# Micro-OLED-Breakout.net
KiCad netlist of a schematic drawn in EAGLE
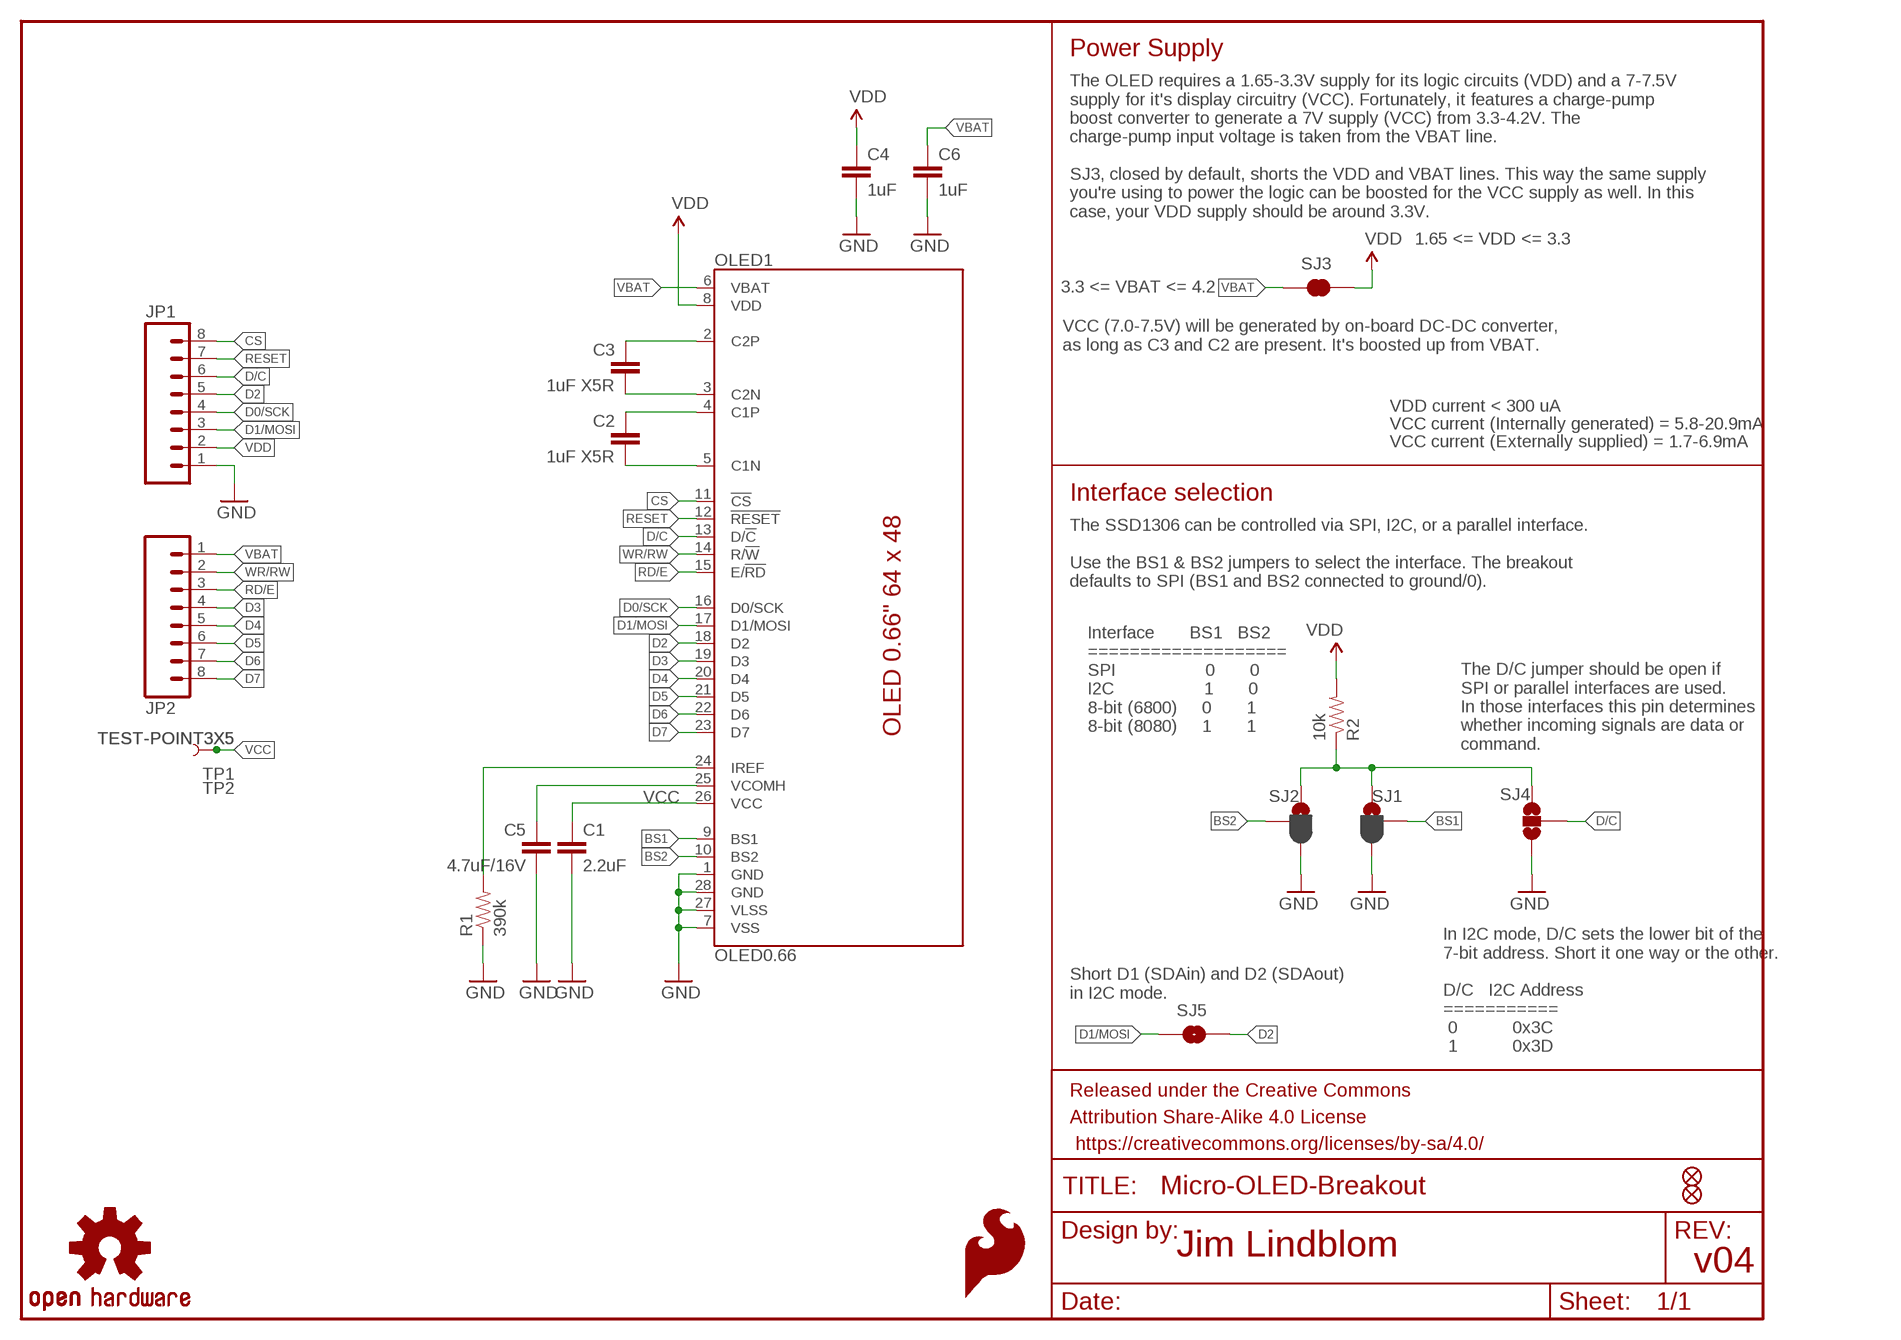
[diagram p0: schematic, sheet 1]

(export (version "E")
  (design (tool "Eeschema 10.0.6"))
  (components
    (comp (ref "C1")
      (value "2.2uF")
      (footprint "eagle-import:0805")
      (libsource (lib "eagle-import") (part "CAP0805"))
    )
    (comp (ref "C2")
      (value "1uF X5R")
      (footprint "eagle-import:0805")
      (libsource (lib "eagle-import") (part "CAP0805"))
    )
    (comp (ref "C3")
      (value "1uF X5R")
      (footprint "eagle-import:0805")
      (libsource (lib "eagle-import") (part "CAP0805"))
    )
    (comp (ref "C4")
      (value "1uF")
      (footprint "eagle-import:0603-CAP")
      (libsource (lib "eagle-import") (part "CAP0603-CAP"))
    )
    (comp (ref "C5")
      (value "4.7uF/16V")
      (footprint "eagle-import:1206")
      (libsource (lib "eagle-import") (part "CAP1206"))
    )
    (comp (ref "C6")
      (value "1uF")
      (footprint "eagle-import:0603-CAP")
      (libsource (lib "eagle-import") (part "CAP0603-CAP"))
    )
    (comp (ref "FID1")
      (value "FIDUCIAL1X2")
      (footprint "eagle-import:FIDUCIAL-1X2")
      (libsource (lib "eagle-import") (part "FIDUCIAL1X2"))
    )
    (comp (ref "FID2")
      (value "FIDUCIAL1X2")
      (footprint "eagle-import:FIDUCIAL-1X2")
      (libsource (lib "eagle-import") (part "FIDUCIAL1X2"))
    )
    (comp (ref "FRAME1")
      (value "FRAME-LETTER")
      (footprint "eagle-import:CREATIVE_COMMONS")
      (libsource (lib "eagle-import") (part "FRAME-LETTER"))
    )
    (comp (ref "JP1")
      (value "M08")
      (footprint "eagle-import:1X08_PIN1_NO_SILK")
      (libsource (lib "eagle-import") (part "M08"))
    )
    (comp (ref "JP2")
      (value "M08")
      (footprint "eagle-import:1X08_PIN1_NO_SILK")
      (libsource (lib "eagle-import") (part "M08"))
    )
    (comp (ref "LOGO3")
      (value "OSHW-LOGOS")
      (footprint "eagle-import:OSHW-LOGO-S")
      (libsource (lib "eagle-import") (part "OSHW-LOGOS"))
    )
    (comp (ref "LOGO4")
      (value "SFE_LOGO_FLAME.1_INCH")
      (footprint "eagle-import:SFE_LOGO_FLAME_.1")
      (libsource (lib "eagle-import") (part "SFE_LOGO_FLAME.1_INCH"))
    )
    (comp (ref "OLED1")
      (value "OLED0.66")
      (footprint "eagle-import:OLED-0.66-64X48")
      (libsource (lib "eagle-import") (part "OLED0.66"))
    )
    (comp (ref "R1")
      (value "390k")
      (footprint "eagle-import:0603-RES")
      (libsource (lib "eagle-import") (part "RESISTOR0603-RES"))
    )
    (comp (ref "R2")
      (value "10k")
      (footprint "eagle-import:0603-RES")
      (libsource (lib "eagle-import") (part "RESISTOR0603-RES"))
    )
    (comp (ref "SJ1")
      (value "BS1")
      (footprint "eagle-import:PAD-JUMPER-3-2OF3_NC_BY_PASTE_YES_SILK_FULL_BOX")
      (libsource (lib "eagle-import") (part "JUMPER-PAD-3-2OF3_NC_BY_PASTE"))
    )
    (comp (ref "SJ2")
      (value "BS2")
      (footprint "eagle-import:PAD-JUMPER-3-2OF3_NC_BY_PASTE_YES_SILK_FULL_BOX")
      (libsource (lib "eagle-import") (part "JUMPER-PAD-3-2OF3_NC_BY_PASTE"))
    )
    (comp (ref "SJ3")
      (value "JUMPER-PAD-2-NC_BY_TRACENO_SILK")
      (footprint "eagle-import:PAD-JUMPER-2-NC_BY_TRACE_NO_SILK")
      (libsource (lib "eagle-import") (part "JUMPER-PAD-2-NC_BY_TRACENO_SILK"))
    )
    (comp (ref "SJ4")
      (value "JUMPER-PAD-3-NOTIGHT")
      (footprint "eagle-import:PAD-JUMPER-3-NO-TIGHT")
      (libsource (lib "eagle-import") (part "JUMPER-PAD-3-NOTIGHT"))
    )
    (comp (ref "SJ5")
      (value "JUMPER-PAD-2-NOYES_SILK")
      (footprint "eagle-import:PAD-JUMPER-2-NO_YES_SILK")
      (libsource (lib "eagle-import") (part "JUMPER-PAD-2-NOYES_SILK"))
    )
    (comp (ref "TP1")
      (value "TEST-POINT3X5")
      (footprint "eagle-import:PAD.03X.05")
      (libsource (lib "eagle-import") (part "TEST-POINT3X5"))
    )
    (comp (ref "TP2")
      (value "TEST-POINT3X5")
      (footprint "eagle-import:PAD.03X.05")
      (libsource (lib "eagle-import") (part "TEST-POINT3X5"))
    )
  )
  (nets
    (net (code "1") (name "BS1") (class "Default")
      (node (ref "OLED1") (pin "9") (pinfunction "BS1_9") (pintype "bidirectional"))
      (node (ref "SJ1") (pin "2") (pinfunction "2_2") (pintype "passive"))
    )
    (net (code "2") (name "BS2") (class "Default")
      (node (ref "OLED1") (pin "10") (pinfunction "BS2_10") (pintype "bidirectional"))
      (node (ref "SJ2") (pin "2") (pinfunction "2_2") (pintype "passive"))
    )
    (net (code "3") (name "CS") (class "Default")
      (node (ref "JP1") (pin "8") (pinfunction "8_8") (pintype "passive"))
      (node (ref "OLED1") (pin "11") (pinfunction "~{CS}_11") (pintype "bidirectional"))
    )
    (net (code "4") (name "D0{slash}SCK") (class "Default")
      (node (ref "JP1") (pin "4") (pinfunction "4_4") (pintype "passive"))
      (node (ref "OLED1") (pin "16") (pinfunction "D0/SCK_16") (pintype "bidirectional"))
    )
    (net (code "5") (name "D1{slash}MOSI") (class "Default")
      (node (ref "JP1") (pin "3") (pinfunction "3_3") (pintype "passive"))
      (node (ref "OLED1") (pin "17") (pinfunction "D1/MOSI_17") (pintype "bidirectional"))
      (node (ref "SJ5") (pin "1") (pinfunction "1_1") (pintype "passive"))
    )
    (net (code "6") (name "D2") (class "Default")
      (node (ref "JP1") (pin "5") (pinfunction "5_5") (pintype "passive"))
      (node (ref "OLED1") (pin "18") (pinfunction "D2_18") (pintype "bidirectional"))
      (node (ref "SJ5") (pin "2") (pinfunction "2_2") (pintype "passive"))
    )
    (net (code "7") (name "D3") (class "Default")
      (node (ref "JP2") (pin "4") (pinfunction "4_4") (pintype "passive"))
      (node (ref "OLED1") (pin "19") (pinfunction "D3_19") (pintype "bidirectional"))
    )
    (net (code "8") (name "D4") (class "Default")
      (node (ref "JP2") (pin "5") (pinfunction "5_5") (pintype "passive"))
      (node (ref "OLED1") (pin "20") (pinfunction "D4_20") (pintype "bidirectional"))
    )
    (net (code "9") (name "D5") (class "Default")
      (node (ref "JP2") (pin "6") (pinfunction "6_6") (pintype "passive"))
      (node (ref "OLED1") (pin "21") (pinfunction "D5_21") (pintype "bidirectional"))
    )
    (net (code "10") (name "D6") (class "Default")
      (node (ref "JP2") (pin "7") (pinfunction "7_7") (pintype "passive"))
      (node (ref "OLED1") (pin "22") (pinfunction "D6_22") (pintype "bidirectional"))
    )
    (net (code "11") (name "D7") (class "Default")
      (node (ref "JP2") (pin "8") (pinfunction "8_8") (pintype "passive"))
      (node (ref "OLED1") (pin "23") (pinfunction "D7_23") (pintype "bidirectional"))
    )
    (net (code "12") (name "D{slash}C") (class "Default")
      (node (ref "JP1") (pin "6") (pinfunction "6_6") (pintype "passive"))
      (node (ref "OLED1") (pin "13") (pinfunction "D/~{C}_13") (pintype "bidirectional"))
      (node (ref "SJ4") (pin "2") (pinfunction "2_2") (pintype "passive"))
    )
    (net (code "13") (name "GND") (class "Default")
      (node (ref "C1") (pin "2") (pinfunction "2_2") (pintype "passive"))
      (node (ref "C4") (pin "2") (pinfunction "2_2") (pintype "passive"))
      (node (ref "C5") (pin "2") (pinfunction "2_2") (pintype "passive"))
      (node (ref "C6") (pin "2") (pinfunction "2_2") (pintype "passive"))
      (node (ref "JP1") (pin "1") (pinfunction "1_1") (pintype "passive"))
      (node (ref "OLED1") (pin "1") (pinfunction "GND_1") (pintype "bidirectional"))
      (node (ref "OLED1") (pin "27") (pinfunction "VLSS_27") (pintype "bidirectional"))
      (node (ref "OLED1") (pin "28") (pinfunction "GND_28") (pintype "bidirectional"))
      (node (ref "OLED1") (pin "7") (pinfunction "VSS_7") (pintype "bidirectional"))
      (node (ref "R1") (pin "1") (pinfunction "1_1") (pintype "passive"))
      (node (ref "SJ1") (pin "3") (pinfunction "3_3") (pintype "passive"))
      (node (ref "SJ2") (pin "3") (pinfunction "3_3") (pintype "passive"))
      (node (ref "SJ4") (pin "3") (pinfunction "3_3") (pintype "passive"))
    )
    (net (code "14") (name "Net-(OLED1-C1N)") (class "Default")
      (node (ref "C2") (pin "2") (pinfunction "2_2") (pintype "passive"))
      (node (ref "OLED1") (pin "5") (pinfunction "C1N_5") (pintype "bidirectional"))
    )
    (net (code "15") (name "Net-(OLED1-C1P)") (class "Default")
      (node (ref "C2") (pin "1") (pinfunction "1_1") (pintype "passive"))
      (node (ref "OLED1") (pin "4") (pinfunction "C1P_4") (pintype "bidirectional"))
    )
    (net (code "16") (name "Net-(OLED1-C2N)") (class "Default")
      (node (ref "C3") (pin "2") (pinfunction "2_2") (pintype "passive"))
      (node (ref "OLED1") (pin "3") (pinfunction "C2N_3") (pintype "bidirectional"))
    )
    (net (code "17") (name "Net-(OLED1-C2P)") (class "Default")
      (node (ref "C3") (pin "1") (pinfunction "1_1") (pintype "passive"))
      (node (ref "OLED1") (pin "2") (pinfunction "C2P_2") (pintype "bidirectional"))
    )
    (net (code "18") (name "Net-(OLED1-IREF)") (class "Default")
      (node (ref "OLED1") (pin "24") (pinfunction "IREF_24") (pintype "bidirectional"))
      (node (ref "R1") (pin "2") (pinfunction "2_2") (pintype "passive"))
    )
    (net (code "19") (name "Net-(OLED1-VCOMH)") (class "Default")
      (node (ref "C5") (pin "1") (pinfunction "1_1") (pintype "passive"))
      (node (ref "OLED1") (pin "25") (pinfunction "VCOMH_25") (pintype "bidirectional"))
    )
    (net (code "20") (name "Net-(R2-Pad1)") (class "Default")
      (node (ref "R2") (pin "1") (pinfunction "1_1") (pintype "passive"))
      (node (ref "SJ1") (pin "1") (pinfunction "1_1") (pintype "passive"))
      (node (ref "SJ2") (pin "1") (pinfunction "1_1") (pintype "passive"))
      (node (ref "SJ4") (pin "1") (pinfunction "1_1") (pintype "passive"))
    )
    (net (code "21") (name "RD{slash}E") (class "Default")
      (node (ref "JP2") (pin "3") (pinfunction "3_3") (pintype "passive"))
      (node (ref "OLED1") (pin "15") (pinfunction "E/~{RD}_15") (pintype "bidirectional"))
    )
    (net (code "22") (name "RESET") (class "Default")
      (node (ref "JP1") (pin "7") (pinfunction "7_7") (pintype "passive"))
      (node (ref "OLED1") (pin "12") (pinfunction "~{RESET}_12") (pintype "bidirectional"))
    )
    (net (code "23") (name "VBAT") (class "Default")
      (node (ref "C6") (pin "1") (pinfunction "1_1") (pintype "passive"))
      (node (ref "JP2") (pin "1") (pinfunction "1_1") (pintype "passive"))
      (node (ref "OLED1") (pin "6") (pinfunction "VBAT_6") (pintype "bidirectional"))
      (node (ref "SJ3") (pin "1") (pinfunction "1_1") (pintype "passive"))
    )
    (net (code "24") (name "VCC") (class "Default")
      (node (ref "C1") (pin "1") (pinfunction "1_1") (pintype "passive"))
      (node (ref "OLED1") (pin "26") (pinfunction "VCC_26") (pintype "bidirectional"))
      (node (ref "TP1") (pin "P$1") (pinfunction "1_P$1") (pintype "bidirectional"))
      (node (ref "TP2") (pin "P$1") (pinfunction "1_P$1") (pintype "bidirectional"))
    )
    (net (code "25") (name "VDD") (class "Default")
      (node (ref "C4") (pin "1") (pinfunction "1_1") (pintype "passive"))
      (node (ref "JP1") (pin "2") (pinfunction "2_2") (pintype "passive"))
      (node (ref "OLED1") (pin "8") (pinfunction "VDD_8") (pintype "bidirectional"))
      (node (ref "R2") (pin "2") (pinfunction "2_2") (pintype "passive"))
      (node (ref "SJ3") (pin "2") (pinfunction "2_2") (pintype "passive"))
    )
    (net (code "26") (name "WR{slash}RW") (class "Default")
      (node (ref "JP2") (pin "2") (pinfunction "2_2") (pintype "passive"))
      (node (ref "OLED1") (pin "14") (pinfunction "R/~{W}_14") (pintype "bidirectional"))
    )
  )
)
